# M900proto.net
KiCad netlist of a schematic drawn in EAGLE
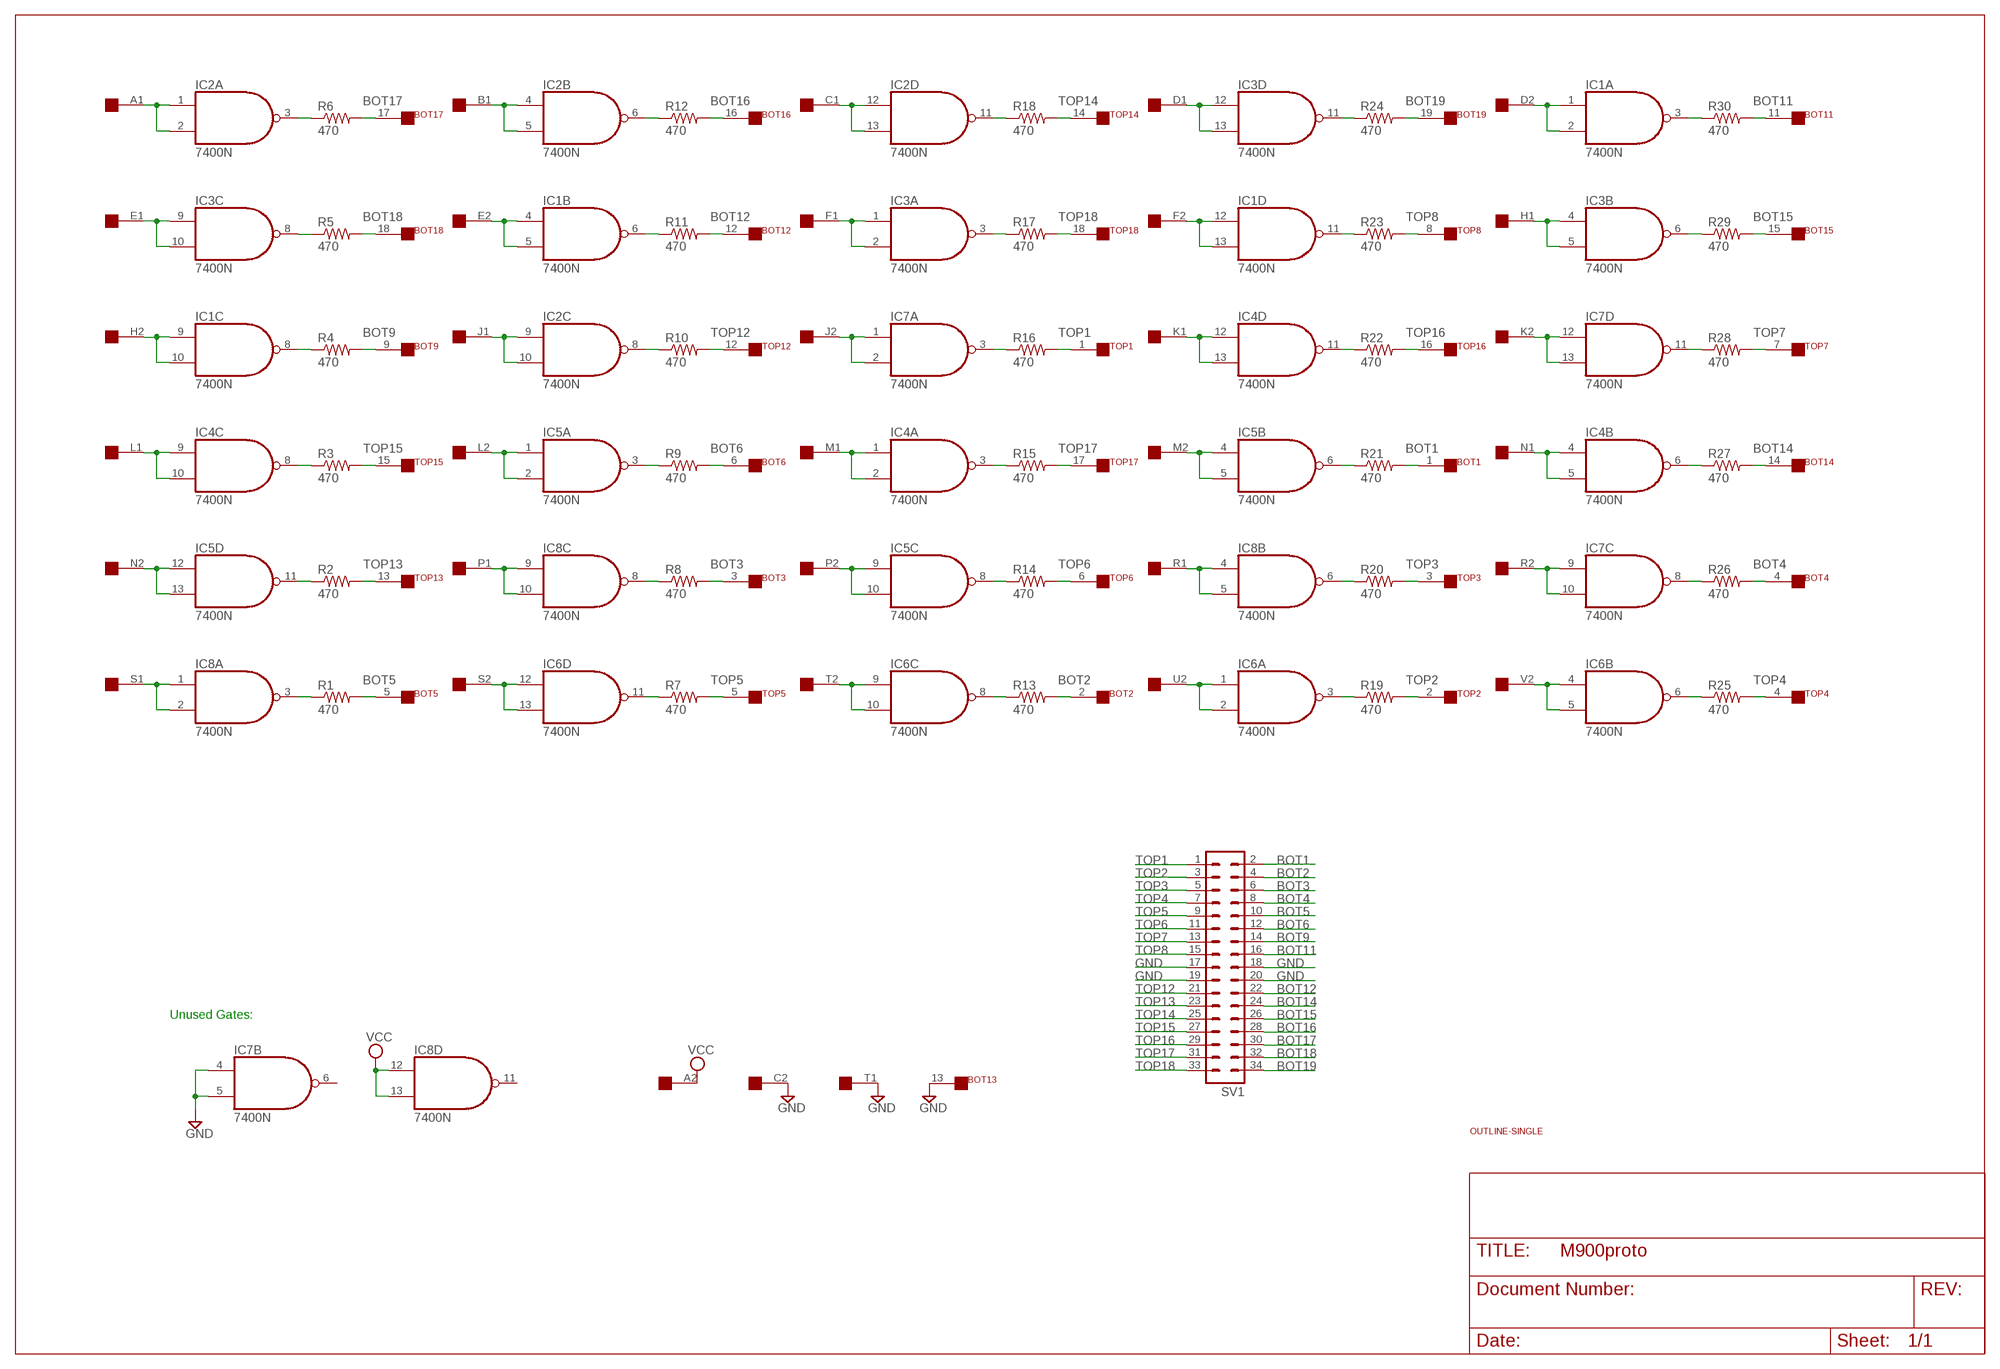
[diagram p0: schematic, sheet 1]

(export (version "E")
  (design (tool "Eeschema 10.0.6"))
  (components
    (comp (ref "BOT")
      (value "FLEX19")
      (footprint "eagle-import:FLEX19")
      (libsource (lib "eagle-import") (part "FLEX19"))
    )
    (comp (ref "EDGE")
      (value "SINGLE")
      (footprint "eagle-import:EDGE-CON2")
      (libsource (lib "eagle-import") (part "SINGLE"))
    )
    (comp (ref "IC1")
      (value "7400N")
      (footprint "eagle-import:DIL14")
      (libsource (lib "eagle-import") (part "7400N"))
    )
    (comp (ref "IC2")
      (value "7400N")
      (footprint "eagle-import:DIL14")
      (libsource (lib "eagle-import") (part "7400N"))
    )
    (comp (ref "IC3")
      (value "7400N")
      (footprint "eagle-import:DIL14")
      (libsource (lib "eagle-import") (part "7400N"))
    )
    (comp (ref "IC4")
      (value "7400N")
      (footprint "eagle-import:DIL14")
      (libsource (lib "eagle-import") (part "7400N"))
    )
    (comp (ref "IC5")
      (value "7400N")
      (footprint "eagle-import:DIL14")
      (libsource (lib "eagle-import") (part "7400N"))
    )
    (comp (ref "IC6")
      (value "7400N")
      (footprint "eagle-import:DIL14")
      (libsource (lib "eagle-import") (part "7400N"))
    )
    (comp (ref "IC7")
      (value "7400N")
      (footprint "eagle-import:DIL14")
      (libsource (lib "eagle-import") (part "7400N"))
    )
    (comp (ref "IC8")
      (value "7400N")
      (footprint "eagle-import:DIL14")
      (libsource (lib "eagle-import") (part "7400N"))
    )
    (comp (ref "R1")
      (value "470")
      (footprint "eagle-import:0207_10")
      (libsource (lib "eagle-import") (part "R-US_0207/10"))
    )
    (comp (ref "R2")
      (value "470")
      (footprint "eagle-import:0207_10")
      (libsource (lib "eagle-import") (part "R-US_0207/10"))
    )
    (comp (ref "R3")
      (value "470")
      (footprint "eagle-import:0207_10")
      (libsource (lib "eagle-import") (part "R-US_0207/10"))
    )
    (comp (ref "R4")
      (value "470")
      (footprint "eagle-import:0207_10")
      (libsource (lib "eagle-import") (part "R-US_0207/10"))
    )
    (comp (ref "R5")
      (value "470")
      (footprint "eagle-import:0207_10")
      (libsource (lib "eagle-import") (part "R-US_0207/10"))
    )
    (comp (ref "R6")
      (value "470")
      (footprint "eagle-import:0207_10")
      (libsource (lib "eagle-import") (part "R-US_0207/10"))
    )
    (comp (ref "R7")
      (value "470")
      (footprint "eagle-import:0207_10")
      (libsource (lib "eagle-import") (part "R-US_0207/10"))
    )
    (comp (ref "R8")
      (value "470")
      (footprint "eagle-import:0207_10")
      (libsource (lib "eagle-import") (part "R-US_0207/10"))
    )
    (comp (ref "R9")
      (value "470")
      (footprint "eagle-import:0207_10")
      (libsource (lib "eagle-import") (part "R-US_0207/10"))
    )
    (comp (ref "R10")
      (value "470")
      (footprint "eagle-import:0207_10")
      (libsource (lib "eagle-import") (part "R-US_0207/10"))
    )
    (comp (ref "R11")
      (value "470")
      (footprint "eagle-import:0207_10")
      (libsource (lib "eagle-import") (part "R-US_0207/10"))
    )
    (comp (ref "R12")
      (value "470")
      (footprint "eagle-import:0207_10")
      (libsource (lib "eagle-import") (part "R-US_0207/10"))
    )
    (comp (ref "R13")
      (value "470")
      (footprint "eagle-import:0207_10")
      (libsource (lib "eagle-import") (part "R-US_0207/10"))
    )
    (comp (ref "R14")
      (value "470")
      (footprint "eagle-import:0207_10")
      (libsource (lib "eagle-import") (part "R-US_0207/10"))
    )
    (comp (ref "R15")
      (value "470")
      (footprint "eagle-import:0207_10")
      (libsource (lib "eagle-import") (part "R-US_0207/10"))
    )
    (comp (ref "R16")
      (value "470")
      (footprint "eagle-import:0207_10")
      (libsource (lib "eagle-import") (part "R-US_0207/10"))
    )
    (comp (ref "R17")
      (value "470")
      (footprint "eagle-import:0207_10")
      (libsource (lib "eagle-import") (part "R-US_0207/10"))
    )
    (comp (ref "R18")
      (value "470")
      (footprint "eagle-import:0207_10")
      (libsource (lib "eagle-import") (part "R-US_0207/10"))
    )
    (comp (ref "R19")
      (value "470")
      (footprint "eagle-import:0207_10")
      (libsource (lib "eagle-import") (part "R-US_0207/10"))
    )
    (comp (ref "R20")
      (value "470")
      (footprint "eagle-import:0207_10")
      (libsource (lib "eagle-import") (part "R-US_0207/10"))
    )
    (comp (ref "R21")
      (value "470")
      (footprint "eagle-import:0207_10")
      (libsource (lib "eagle-import") (part "R-US_0207/10"))
    )
    (comp (ref "R22")
      (value "470")
      (footprint "eagle-import:0207_10")
      (libsource (lib "eagle-import") (part "R-US_0207/10"))
    )
    (comp (ref "R23")
      (value "470")
      (footprint "eagle-import:0207_10")
      (libsource (lib "eagle-import") (part "R-US_0207/10"))
    )
    (comp (ref "R24")
      (value "470")
      (footprint "eagle-import:0207_10")
      (libsource (lib "eagle-import") (part "R-US_0207/10"))
    )
    (comp (ref "R25")
      (value "470")
      (footprint "eagle-import:0207_10")
      (libsource (lib "eagle-import") (part "R-US_0207/10"))
    )
    (comp (ref "R26")
      (value "470")
      (footprint "eagle-import:0207_10")
      (libsource (lib "eagle-import") (part "R-US_0207/10"))
    )
    (comp (ref "R27")
      (value "470")
      (footprint "eagle-import:0207_10")
      (libsource (lib "eagle-import") (part "R-US_0207/10"))
    )
    (comp (ref "R28")
      (value "470")
      (footprint "eagle-import:0207_10")
      (libsource (lib "eagle-import") (part "R-US_0207/10"))
    )
    (comp (ref "R29")
      (value "470")
      (footprint "eagle-import:0207_10")
      (libsource (lib "eagle-import") (part "R-US_0207/10"))
    )
    (comp (ref "R30")
      (value "470")
      (footprint "eagle-import:0207_10")
      (libsource (lib "eagle-import") (part "R-US_0207/10"))
    )
    (comp (ref "SV1")
      (value "MA17-2")
      (footprint "eagle-import:MA17-2")
      (libsource (lib "eagle-import") (part "MA17-2"))
    )
    (comp (ref "TOP")
      (value "FLEX19")
      (footprint "eagle-import:FLEX19")
      (libsource (lib "eagle-import") (part "FLEX19"))
    )
    (comp (ref "U$2")
      (value "OUTLINE-SINGLE")
      (footprint "eagle-import:SINGLE")
      (libsource (lib "eagle-import") (part "OUTLINE-SINGLE"))
    )
  )
  (nets
    (net (code "1") (name "/BOT1") (class "Default")
      (node (ref "BOT") (pin "1") (pinfunction "1_1") (pintype "passive"))
      (node (ref "R21") (pin "2") (pinfunction "2_2") (pintype "passive"))
      (node (ref "SV1") (pin "2") (pinfunction "2_2") (pintype "passive"))
    )
    (net (code "2") (name "/BOT2") (class "Default")
      (node (ref "BOT") (pin "2") (pinfunction "1_2") (pintype "passive"))
      (node (ref "R13") (pin "2") (pinfunction "2_2") (pintype "passive"))
      (node (ref "SV1") (pin "4") (pinfunction "4_4") (pintype "passive"))
    )
    (net (code "3") (name "/BOT3") (class "Default")
      (node (ref "BOT") (pin "3") (pinfunction "1_3") (pintype "passive"))
      (node (ref "R8") (pin "2") (pinfunction "2_2") (pintype "passive"))
      (node (ref "SV1") (pin "6") (pinfunction "6_6") (pintype "passive"))
    )
    (net (code "4") (name "/BOT4") (class "Default")
      (node (ref "BOT") (pin "4") (pinfunction "1_4") (pintype "passive"))
      (node (ref "R26") (pin "2") (pinfunction "2_2") (pintype "passive"))
      (node (ref "SV1") (pin "8") (pinfunction "8_8") (pintype "passive"))
    )
    (net (code "5") (name "/BOT5") (class "Default")
      (node (ref "BOT") (pin "5") (pinfunction "1_5") (pintype "passive"))
      (node (ref "R1") (pin "2") (pinfunction "2_2") (pintype "passive"))
      (node (ref "SV1") (pin "10") (pinfunction "10_10") (pintype "passive"))
    )
    (net (code "6") (name "/BOT6") (class "Default")
      (node (ref "BOT") (pin "6") (pinfunction "1_6") (pintype "passive"))
      (node (ref "R9") (pin "2") (pinfunction "2_2") (pintype "passive"))
      (node (ref "SV1") (pin "12") (pinfunction "12_12") (pintype "passive"))
    )
    (net (code "7") (name "/BOT9") (class "Default")
      (node (ref "BOT") (pin "9") (pinfunction "1_9") (pintype "passive"))
      (node (ref "R4") (pin "2") (pinfunction "2_2") (pintype "passive"))
      (node (ref "SV1") (pin "14") (pinfunction "14_14") (pintype "passive"))
    )
    (net (code "8") (name "/BOT11") (class "Default")
      (node (ref "BOT") (pin "11") (pinfunction "1_11") (pintype "passive"))
      (node (ref "R30") (pin "2") (pinfunction "2_2") (pintype "passive"))
      (node (ref "SV1") (pin "16") (pinfunction "16_16") (pintype "passive"))
    )
    (net (code "9") (name "/BOT12") (class "Default")
      (node (ref "BOT") (pin "12") (pinfunction "1_12") (pintype "passive"))
      (node (ref "R11") (pin "2") (pinfunction "2_2") (pintype "passive"))
      (node (ref "SV1") (pin "22") (pinfunction "22_22") (pintype "passive"))
    )
    (net (code "10") (name "/BOT14") (class "Default")
      (node (ref "BOT") (pin "14") (pinfunction "1_14") (pintype "passive"))
      (node (ref "R27") (pin "2") (pinfunction "2_2") (pintype "passive"))
      (node (ref "SV1") (pin "24") (pinfunction "24_24") (pintype "passive"))
    )
    (net (code "11") (name "/BOT15") (class "Default")
      (node (ref "BOT") (pin "15") (pinfunction "1_15") (pintype "passive"))
      (node (ref "R29") (pin "2") (pinfunction "2_2") (pintype "passive"))
      (node (ref "SV1") (pin "26") (pinfunction "26_26") (pintype "passive"))
    )
    (net (code "12") (name "/BOT16") (class "Default")
      (node (ref "BOT") (pin "16") (pinfunction "1_16") (pintype "passive"))
      (node (ref "R12") (pin "2") (pinfunction "2_2") (pintype "passive"))
      (node (ref "SV1") (pin "28") (pinfunction "28_28") (pintype "passive"))
    )
    (net (code "13") (name "/BOT17") (class "Default")
      (node (ref "BOT") (pin "17") (pinfunction "1_17") (pintype "passive"))
      (node (ref "R6") (pin "2") (pinfunction "2_2") (pintype "passive"))
      (node (ref "SV1") (pin "30") (pinfunction "30_30") (pintype "passive"))
    )
    (net (code "14") (name "/BOT18") (class "Default")
      (node (ref "BOT") (pin "18") (pinfunction "1_18") (pintype "passive"))
      (node (ref "R5") (pin "2") (pinfunction "2_2") (pintype "passive"))
      (node (ref "SV1") (pin "32") (pinfunction "32_32") (pintype "passive"))
    )
    (net (code "15") (name "/BOT19") (class "Default")
      (node (ref "BOT") (pin "19") (pinfunction "1_19") (pintype "passive"))
      (node (ref "R24") (pin "2") (pinfunction "2_2") (pintype "passive"))
      (node (ref "SV1") (pin "34") (pinfunction "34_34") (pintype "passive"))
    )
    (net (code "16") (name "/TOP1") (class "Default")
      (node (ref "R16") (pin "2") (pinfunction "2_2") (pintype "passive"))
      (node (ref "SV1") (pin "1") (pinfunction "1_1") (pintype "passive"))
      (node (ref "TOP") (pin "1") (pinfunction "1_1") (pintype "passive"))
    )
    (net (code "17") (name "/TOP2") (class "Default")
      (node (ref "R19") (pin "2") (pinfunction "2_2") (pintype "passive"))
      (node (ref "SV1") (pin "3") (pinfunction "3_3") (pintype "passive"))
      (node (ref "TOP") (pin "2") (pinfunction "1_2") (pintype "passive"))
    )
    (net (code "18") (name "/TOP3") (class "Default")
      (node (ref "R20") (pin "2") (pinfunction "2_2") (pintype "passive"))
      (node (ref "SV1") (pin "5") (pinfunction "5_5") (pintype "passive"))
      (node (ref "TOP") (pin "3") (pinfunction "1_3") (pintype "passive"))
    )
    (net (code "19") (name "/TOP4") (class "Default")
      (node (ref "R25") (pin "2") (pinfunction "2_2") (pintype "passive"))
      (node (ref "SV1") (pin "7") (pinfunction "7_7") (pintype "passive"))
      (node (ref "TOP") (pin "4") (pinfunction "1_4") (pintype "passive"))
    )
    (net (code "20") (name "/TOP5") (class "Default")
      (node (ref "R7") (pin "2") (pinfunction "2_2") (pintype "passive"))
      (node (ref "SV1") (pin "9") (pinfunction "9_9") (pintype "passive"))
      (node (ref "TOP") (pin "5") (pinfunction "1_5") (pintype "passive"))
    )
    (net (code "21") (name "/TOP6") (class "Default")
      (node (ref "R14") (pin "2") (pinfunction "2_2") (pintype "passive"))
      (node (ref "SV1") (pin "11") (pinfunction "11_11") (pintype "passive"))
      (node (ref "TOP") (pin "6") (pinfunction "1_6") (pintype "passive"))
    )
    (net (code "22") (name "/TOP7") (class "Default")
      (node (ref "R28") (pin "2") (pinfunction "2_2") (pintype "passive"))
      (node (ref "SV1") (pin "13") (pinfunction "13_13") (pintype "passive"))
      (node (ref "TOP") (pin "7") (pinfunction "1_7") (pintype "passive"))
    )
    (net (code "23") (name "/TOP8") (class "Default")
      (node (ref "R23") (pin "2") (pinfunction "2_2") (pintype "passive"))
      (node (ref "SV1") (pin "15") (pinfunction "15_15") (pintype "passive"))
      (node (ref "TOP") (pin "8") (pinfunction "1_8") (pintype "passive"))
    )
    (net (code "24") (name "/TOP12") (class "Default")
      (node (ref "R10") (pin "2") (pinfunction "2_2") (pintype "passive"))
      (node (ref "SV1") (pin "21") (pinfunction "21_21") (pintype "passive"))
      (node (ref "TOP") (pin "12") (pinfunction "1_12") (pintype "passive"))
    )
    (net (code "25") (name "/TOP13") (class "Default")
      (node (ref "R2") (pin "2") (pinfunction "2_2") (pintype "passive"))
      (node (ref "SV1") (pin "23") (pinfunction "23_23") (pintype "passive"))
      (node (ref "TOP") (pin "13") (pinfunction "1_13") (pintype "passive"))
    )
    (net (code "26") (name "/TOP14") (class "Default")
      (node (ref "R18") (pin "2") (pinfunction "2_2") (pintype "passive"))
      (node (ref "SV1") (pin "25") (pinfunction "25_25") (pintype "passive"))
      (node (ref "TOP") (pin "14") (pinfunction "1_14") (pintype "passive"))
    )
    (net (code "27") (name "/TOP15") (class "Default")
      (node (ref "R3") (pin "2") (pinfunction "2_2") (pintype "passive"))
      (node (ref "SV1") (pin "27") (pinfunction "27_27") (pintype "passive"))
      (node (ref "TOP") (pin "15") (pinfunction "1_15") (pintype "passive"))
    )
    (net (code "28") (name "/TOP16") (class "Default")
      (node (ref "R22") (pin "2") (pinfunction "2_2") (pintype "passive"))
      (node (ref "SV1") (pin "29") (pinfunction "29_29") (pintype "passive"))
      (node (ref "TOP") (pin "16") (pinfunction "1_16") (pintype "passive"))
    )
    (net (code "29") (name "/TOP17") (class "Default")
      (node (ref "R15") (pin "2") (pinfunction "2_2") (pintype "passive"))
      (node (ref "SV1") (pin "31") (pinfunction "31_31") (pintype "passive"))
      (node (ref "TOP") (pin "17") (pinfunction "1_17") (pintype "passive"))
    )
    (net (code "30") (name "/TOP18") (class "Default")
      (node (ref "R17") (pin "2") (pinfunction "2_2") (pintype "passive"))
      (node (ref "SV1") (pin "33") (pinfunction "33_33") (pintype "passive"))
      (node (ref "TOP") (pin "18") (pinfunction "1_18") (pintype "passive"))
    )
    (net (code "31") (name "GND") (class "Default")
      (node (ref "BOT") (pin "13") (pinfunction "1_13") (pintype "passive"))
      (node (ref "EDGE") (pin "C2") (pinfunction "1_C2") (pintype "bidirectional"))
      (node (ref "EDGE") (pin "T1") (pinfunction "1_T1") (pintype "bidirectional"))
      (node (ref "IC7") (pin "4") (pinfunction "I0_4") (pintype "input"))
      (node (ref "IC7") (pin "5") (pinfunction "I1_5") (pintype "input"))
      (node (ref "SV1") (pin "17") (pinfunction "17_17") (pintype "passive"))
      (node (ref "SV1") (pin "18") (pinfunction "18_18") (pintype "passive"))
      (node (ref "SV1") (pin "19") (pinfunction "19_19") (pintype "passive"))
      (node (ref "SV1") (pin "20") (pinfunction "20_20") (pintype "passive"))
    )
    (net (code "32") (name "Net-(EDGEA-1)") (class "Default")
      (node (ref "EDGE") (pin "A1") (pinfunction "1_A1") (pintype "bidirectional"))
      (node (ref "IC2") (pin "1") (pinfunction "I0_1") (pintype "input"))
      (node (ref "IC2") (pin "2") (pinfunction "I1_2") (pintype "input"))
    )
    (net (code "33") (name "Net-(EDGEAA-1)") (class "Default")
      (node (ref "EDGE") (pin "R1") (pinfunction "1_R1") (pintype "bidirectional"))
      (node (ref "IC8") (pin "4") (pinfunction "I0_4") (pintype "input"))
      (node (ref "IC8") (pin "5") (pinfunction "I1_5") (pintype "input"))
    )
    (net (code "34") (name "Net-(EDGEAB-1)") (class "Default")
      (node (ref "EDGE") (pin "R2") (pinfunction "1_R2") (pintype "bidirectional"))
      (node (ref "IC7") (pin "10") (pinfunction "I1_10") (pintype "input"))
      (node (ref "IC7") (pin "9") (pinfunction "I0_9") (pintype "input"))
    )
    (net (code "35") (name "Net-(EDGEAC-1)") (class "Default")
      (node (ref "EDGE") (pin "S1") (pinfunction "1_S1") (pintype "bidirectional"))
      (node (ref "IC8") (pin "1") (pinfunction "I0_1") (pintype "input"))
      (node (ref "IC8") (pin "2") (pinfunction "I1_2") (pintype "input"))
    )
    (net (code "36") (name "Net-(EDGEAD-1)") (class "Default")
      (node (ref "EDGE") (pin "S2") (pinfunction "1_S2") (pintype "bidirectional"))
      (node (ref "IC6") (pin "12") (pinfunction "I0_12") (pintype "input"))
      (node (ref "IC6") (pin "13") (pinfunction "I1_13") (pintype "input"))
    )
    (net (code "37") (name "Net-(EDGEAF-1)") (class "Default")
      (node (ref "EDGE") (pin "T2") (pinfunction "1_T2") (pintype "bidirectional"))
      (node (ref "IC6") (pin "10") (pinfunction "I1_10") (pintype "input"))
      (node (ref "IC6") (pin "9") (pinfunction "I0_9") (pintype "input"))
    )
    (net (code "38") (name "Net-(EDGEAH-1)") (class "Default")
      (node (ref "EDGE") (pin "U2") (pinfunction "1_U2") (pintype "bidirectional"))
      (node (ref "IC6") (pin "1") (pinfunction "I0_1") (pintype "input"))
      (node (ref "IC6") (pin "2") (pinfunction "I1_2") (pintype "input"))
    )
    (net (code "39") (name "Net-(EDGEAJ-1)") (class "Default")
      (node (ref "EDGE") (pin "V2") (pinfunction "1_V2") (pintype "bidirectional"))
      (node (ref "IC6") (pin "4") (pinfunction "I0_4") (pintype "input"))
      (node (ref "IC6") (pin "5") (pinfunction "I1_5") (pintype "input"))
    )
    (net (code "40") (name "Net-(EDGEC-1)") (class "Default")
      (node (ref "EDGE") (pin "B1") (pinfunction "1_B1") (pintype "bidirectional"))
      (node (ref "IC2") (pin "4") (pinfunction "I0_4") (pintype "input"))
      (node (ref "IC2") (pin "5") (pinfunction "I1_5") (pintype "input"))
    )
    (net (code "41") (name "Net-(EDGEE-1)") (class "Default")
      (node (ref "EDGE") (pin "C1") (pinfunction "1_C1") (pintype "bidirectional"))
      (node (ref "IC2") (pin "12") (pinfunction "I0_12") (pintype "input"))
      (node (ref "IC2") (pin "13") (pinfunction "I1_13") (pintype "input"))
    )
    (net (code "42") (name "Net-(EDGEG-1)") (class "Default")
      (node (ref "EDGE") (pin "D1") (pinfunction "1_D1") (pintype "bidirectional"))
      (node (ref "IC3") (pin "12") (pinfunction "I0_12") (pintype "input"))
      (node (ref "IC3") (pin "13") (pinfunction "I1_13") (pintype "input"))
    )
    (net (code "43") (name "Net-(EDGEH-1)") (class "Default")
      (node (ref "EDGE") (pin "D2") (pinfunction "1_D2") (pintype "bidirectional"))
      (node (ref "IC1") (pin "1") (pinfunction "I0_1") (pintype "input"))
      (node (ref "IC1") (pin "2") (pinfunction "I1_2") (pintype "input"))
    )
    (net (code "44") (name "Net-(EDGEI-1)") (class "Default")
      (node (ref "EDGE") (pin "E1") (pinfunction "1_E1") (pintype "bidirectional"))
      (node (ref "IC3") (pin "10") (pinfunction "I1_10") (pintype "input"))
      (node (ref "IC3") (pin "9") (pinfunction "I0_9") (pintype "input"))
    )
    (net (code "45") (name "Net-(EDGEJ-1)") (class "Default")
      (node (ref "EDGE") (pin "E2") (pinfunction "1_E2") (pintype "bidirectional"))
      (node (ref "IC1") (pin "4") (pinfunction "I0_4") (pintype "input"))
      (node (ref "IC1") (pin "5") (pinfunction "I1_5") (pintype "input"))
    )
    (net (code "46") (name "Net-(EDGEK-1)") (class "Default")
      (node (ref "EDGE") (pin "F1") (pinfunction "1_F1") (pintype "bidirectional"))
      (node (ref "IC3") (pin "1") (pinfunction "I0_1") (pintype "input"))
      (node (ref "IC3") (pin "2") (pinfunction "I1_2") (pintype "input"))
    )
    (net (code "47") (name "Net-(EDGEL-1)") (class "Default")
      (node (ref "EDGE") (pin "F2") (pinfunction "1_F2") (pintype "bidirectional"))
      (node (ref "IC1") (pin "12") (pinfunction "I0_12") (pintype "input"))
      (node (ref "IC1") (pin "13") (pinfunction "I1_13") (pintype "input"))
    )
    (net (code "48") (name "Net-(EDGEM-1)") (class "Default")
      (node (ref "EDGE") (pin "H1") (pinfunction "1_H1") (pintype "bidirectional"))
      (node (ref "IC3") (pin "4") (pinfunction "I0_4") (pintype "input"))
      (node (ref "IC3") (pin "5") (pinfunction "I1_5") (pintype "input"))
    )
    (net (code "49") (name "Net-(EDGEN-1)") (class "Default")
      (node (ref "EDGE") (pin "H2") (pinfunction "1_H2") (pintype "bidirectional"))
      (node (ref "IC1") (pin "10") (pinfunction "I1_10") (pintype "input"))
      (node (ref "IC1") (pin "9") (pinfunction "I0_9") (pintype "input"))
    )
    (net (code "50") (name "Net-(EDGEO-1)") (class "Default")
      (node (ref "EDGE") (pin "J1") (pinfunction "1_J1") (pintype "bidirectional"))
      (node (ref "IC2") (pin "10") (pinfunction "I1_10") (pintype "input"))
      (node (ref "IC2") (pin "9") (pinfunction "I0_9") (pintype "input"))
    )
    (net (code "51") (name "Net-(EDGEP-1)") (class "Default")
      (node (ref "EDGE") (pin "J2") (pinfunction "1_J2") (pintype "bidirectional"))
      (node (ref "IC7") (pin "1") (pinfunction "I0_1") (pintype "input"))
      (node (ref "IC7") (pin "2") (pinfunction "I1_2") (pintype "input"))
    )
    (net (code "52") (name "Net-(EDGEQ-1)") (class "Default")
      (node (ref "EDGE") (pin "K1") (pinfunction "1_K1") (pintype "bidirectional"))
      (node (ref "IC4") (pin "12") (pinfunction "I0_12") (pintype "input"))
      (node (ref "IC4") (pin "13") (pinfunction "I1_13") (pintype "input"))
    )
    (net (code "53") (name "Net-(EDGER-1)") (class "Default")
      (node (ref "EDGE") (pin "K2") (pinfunction "1_K2") (pintype "bidirectional"))
      (node (ref "IC7") (pin "12") (pinfunction "I0_12") (pintype "input"))
      (node (ref "IC7") (pin "13") (pinfunction "I1_13") (pintype "input"))
    )
    (net (code "54") (name "Net-(EDGES-1)") (class "Default")
      (node (ref "EDGE") (pin "L1") (pinfunction "1_L1") (pintype "bidirectional"))
      (node (ref "IC4") (pin "10") (pinfunction "I1_10") (pintype "input"))
      (node (ref "IC4") (pin "9") (pinfunction "I0_9") (pintype "input"))
    )
    (net (code "55") (name "Net-(EDGET-1)") (class "Default")
      (node (ref "EDGE") (pin "L2") (pinfunction "1_L2") (pintype "bidirectional"))
      (node (ref "IC5") (pin "1") (pinfunction "I0_1") (pintype "input"))
      (node (ref "IC5") (pin "2") (pinfunction "I1_2") (pintype "input"))
    )
    (net (code "56") (name "Net-(EDGEU-1)") (class "Default")
      (node (ref "EDGE") (pin "M1") (pinfunction "1_M1") (pintype "bidirectional"))
      (node (ref "IC4") (pin "1") (pinfunction "I0_1") (pintype "input"))
      (node (ref "IC4") (pin "2") (pinfunction "I1_2") (pintype "input"))
    )
    (net (code "57") (name "Net-(EDGEV-1)") (class "Default")
      (node (ref "EDGE") (pin "M2") (pinfunction "1_M2") (pintype "bidirectional"))
      (node (ref "IC5") (pin "4") (pinfunction "I0_4") (pintype "input"))
      (node (ref "IC5") (pin "5") (pinfunction "I1_5") (pintype "input"))
    )
    (net (code "58") (name "Net-(EDGEW-1)") (class "Default")
      (node (ref "EDGE") (pin "N1") (pinfunction "1_N1") (pintype "bidirectional"))
      (node (ref "IC4") (pin "4") (pinfunction "I0_4") (pintype "input"))
      (node (ref "IC4") (pin "5") (pinfunction "I1_5") (pintype "input"))
    )
    (net (code "59") (name "Net-(EDGEX-1)") (class "Default")
      (node (ref "EDGE") (pin "N2") (pinfunction "1_N2") (pintype "bidirectional"))
      (node (ref "IC5") (pin "12") (pinfunction "I0_12") (pintype "input"))
      (node (ref "IC5") (pin "13") (pinfunction "I1_13") (pintype "input"))
    )
    (net (code "60") (name "Net-(EDGEY-1)") (class "Default")
      (node (ref "EDGE") (pin "P1") (pinfunction "1_P1") (pintype "bidirectional"))
      (node (ref "IC8") (pin "10") (pinfunction "I1_10") (pintype "input"))
      (node (ref "IC8") (pin "9") (pinfunction "I0_9") (pintype "input"))
    )
    (net (code "61") (name "Net-(EDGEZ-1)") (class "Default")
      (node (ref "EDGE") (pin "P2") (pinfunction "1_P2") (pintype "bidirectional"))
      (node (ref "IC5") (pin "10") (pinfunction "I1_10") (pintype "input"))
      (node (ref "IC5") (pin "9") (pinfunction "I0_9") (pintype "input"))
    )
    (net (code "62") (name "Net-(IC1A-O)") (class "Default")
      (node (ref "IC1") (pin "3") (pinfunction "O_3") (pintype "output"))
      (node (ref "R30") (pin "1") (pinfunction "1_1") (pintype "passive"))
    )
    (net (code "63") (name "Net-(IC1B-O)") (class "Default")
      (node (ref "IC1") (pin "6") (pinfunction "O_6") (pintype "output"))
      (node (ref "R11") (pin "1") (pinfunction "1_1") (pintype "passive"))
    )
    (net (code "64") (name "Net-(IC1C-O)") (class "Default")
      (node (ref "IC1") (pin "8") (pinfunction "O_8") (pintype "output"))
      (node (ref "R4") (pin "1") (pinfunction "1_1") (pintype "passive"))
    )
    (net (code "65") (name "Net-(IC1D-O)") (class "Default")
      (node (ref "IC1") (pin "11") (pinfunction "O_11") (pintype "output"))
      (node (ref "R23") (pin "1") (pinfunction "1_1") (pintype "passive"))
    )
    (net (code "66") (name "Net-(IC2A-O)") (class "Default")
      (node (ref "IC2") (pin "3") (pinfunction "O_3") (pintype "output"))
      (node (ref "R6") (pin "1") (pinfunction "1_1") (pintype "passive"))
    )
    (net (code "67") (name "Net-(IC2B-O)") (class "Default")
      (node (ref "IC2") (pin "6") (pinfunction "O_6") (pintype "output"))
      (node (ref "R12") (pin "1") (pinfunction "1_1") (pintype "passive"))
    )
    (net (code "68") (name "Net-(IC2C-O)") (class "Default")
      (node (ref "IC2") (pin "8") (pinfunction "O_8") (pintype "output"))
      (node (ref "R10") (pin "1") (pinfunction "1_1") (pintype "passive"))
    )
    (net (code "69") (name "Net-(IC2D-O)") (class "Default")
      (node (ref "IC2") (pin "11") (pinfunction "O_11") (pintype "output"))
      (node (ref "R18") (pin "1") (pinfunction "1_1") (pintype "passive"))
    )
    (net (code "70") (name "Net-(IC3A-O)") (class "Default")
      (node (ref "IC3") (pin "3") (pinfunction "O_3") (pintype "output"))
      (node (ref "R17") (pin "1") (pinfunction "1_1") (pintype "passive"))
    )
    (net (code "71") (name "Net-(IC3B-O)") (class "Default")
      (node (ref "IC3") (pin "6") (pinfunction "O_6") (pintype "output"))
      (node (ref "R29") (pin "1") (pinfunction "1_1") (pintype "passive"))
    )
    (net (code "72") (name "Net-(IC3C-O)") (class "Default")
      (node (ref "IC3") (pin "8") (pinfunction "O_8") (pintype "output"))
      (node (ref "R5") (pin "1") (pinfunction "1_1") (pintype "passive"))
    )
    (net (code "73") (name "Net-(IC3D-O)") (class "Default")
      (node (ref "IC3") (pin "11") (pinfunction "O_11") (pintype "output"))
      (node (ref "R24") (pin "1") (pinfunction "1_1") (pintype "passive"))
    )
    (net (code "74") (name "Net-(IC4A-O)") (class "Default")
      (node (ref "IC4") (pin "3") (pinfunction "O_3") (pintype "output"))
      (node (ref "R15") (pin "1") (pinfunction "1_1") (pintype "passive"))
    )
    (net (code "75") (name "Net-(IC4B-O)") (class "Default")
      (node (ref "IC4") (pin "6") (pinfunction "O_6") (pintype "output"))
      (node (ref "R27") (pin "1") (pinfunction "1_1") (pintype "passive"))
    )
    (net (code "76") (name "Net-(IC4C-O)") (class "Default")
      (node (ref "IC4") (pin "8") (pinfunction "O_8") (pintype "output"))
      (node (ref "R3") (pin "1") (pinfunction "1_1") (pintype "passive"))
    )
    (net (code "77") (name "Net-(IC4D-O)") (class "Default")
      (node (ref "IC4") (pin "11") (pinfunction "O_11") (pintype "output"))
      (node (ref "R22") (pin "1") (pinfunction "1_1") (pintype "passive"))
    )
    (net (code "78") (name "Net-(IC5A-O)") (class "Default")
      (node (ref "IC5") (pin "3") (pinfunction "O_3") (pintype "output"))
      (node (ref "R9") (pin "1") (pinfunction "1_1") (pintype "passive"))
    )
    (net (code "79") (name "Net-(IC5B-O)") (class "Default")
      (node (ref "IC5") (pin "6") (pinfunction "O_6") (pintype "output"))
      (node (ref "R21") (pin "1") (pinfunction "1_1") (pintype "passive"))
    )
    (net (code "80") (name "Net-(IC5C-O)") (class "Default")
      (node (ref "IC5") (pin "8") (pinfunction "O_8") (pintype "output"))
      (node (ref "R14") (pin "1") (pinfunction "1_1") (pintype "passive"))
    )
    (net (code "81") (name "Net-(IC5D-O)") (class "Default")
      (node (ref "IC5") (pin "11") (pinfunction "O_11") (pintype "output"))
      (node (ref "R2") (pin "1") (pinfunction "1_1") (pintype "passive"))
    )
    (net (code "82") (name "Net-(IC6A-O)") (class "Default")
      (node (ref "IC6") (pin "3") (pinfunction "O_3") (pintype "output"))
      (node (ref "R19") (pin "1") (pinfunction "1_1") (pintype "passive"))
    )
    (net (code "83") (name "Net-(IC6B-O)") (class "Default")
      (node (ref "IC6") (pin "6") (pinfunction "O_6") (pintype "output"))
      (node (ref "R25") (pin "1") (pinfunction "1_1") (pintype "passive"))
    )
    (net (code "84") (name "Net-(IC6C-O)") (class "Default")
      (node (ref "IC6") (pin "8") (pinfunction "O_8") (pintype "output"))
      (node (ref "R13") (pin "1") (pinfunction "1_1") (pintype "passive"))
    )
    (net (code "85") (name "Net-(IC6D-O)") (class "Default")
      (node (ref "IC6") (pin "11") (pinfunction "O_11") (pintype "output"))
      (node (ref "R7") (pin "1") (pinfunction "1_1") (pintype "passive"))
    )
    (net (code "86") (name "Net-(IC7A-O)") (class "Default")
      (node (ref "IC7") (pin "3") (pinfunction "O_3") (pintype "output"))
      (node (ref "R16") (pin "1") (pinfunction "1_1") (pintype "passive"))
    )
    (net (code "87") (name "Net-(IC7C-O)") (class "Default")
      (node (ref "IC7") (pin "8") (pinfunction "O_8") (pintype "output"))
      (node (ref "R26") (pin "1") (pinfunction "1_1") (pintype "passive"))
    )
    (net (code "88") (name "Net-(IC7D-O)") (class "Default")
      (node (ref "IC7") (pin "11") (pinfunction "O_11") (pintype "output"))
      (node (ref "R28") (pin "1") (pinfunction "1_1") (pintype "passive"))
    )
    (net (code "89") (name "Net-(IC8A-O)") (class "Default")
      (node (ref "IC8") (pin "3") (pinfunction "O_3") (pintype "output"))
      (node (ref "R1") (pin "1") (pinfunction "1_1") (pintype "passive"))
    )
    (net (code "90") (name "Net-(IC8B-O)") (class "Default")
      (node (ref "IC8") (pin "6") (pinfunction "O_6") (pintype "output"))
      (node (ref "R20") (pin "1") (pinfunction "1_1") (pintype "passive"))
    )
    (net (code "91") (name "Net-(IC8C-O)") (class "Default")
      (node (ref "IC8") (pin "8") (pinfunction "O_8") (pintype "output"))
      (node (ref "R8") (pin "1") (pinfunction "1_1") (pintype "passive"))
    )
    (net (code "92") (name "VCC") (class "Default")
      (node (ref "EDGE") (pin "A2") (pinfunction "1_A2") (pintype "bidirectional"))
      (node (ref "IC8") (pin "12") (pinfunction "I0_12") (pintype "input"))
      (node (ref "IC8") (pin "13") (pinfunction "I1_13") (pintype "input"))
    )
    (net (code "93") (name "unconnected-(IC7B-O-Pad6)") (class "Default")
      (node (ref "IC7") (pin "6") (pinfunction "O_6") (pintype "output"))
    )
    (net (code "94") (name "unconnected-(IC8D-O-Pad11)") (class "Default")
      (node (ref "IC8") (pin "11") (pinfunction "O_11") (pintype "output"))
    )
  )
)
